# USBtoTTL.net
KiCad netlist of a schematic drawn in Altium Designer
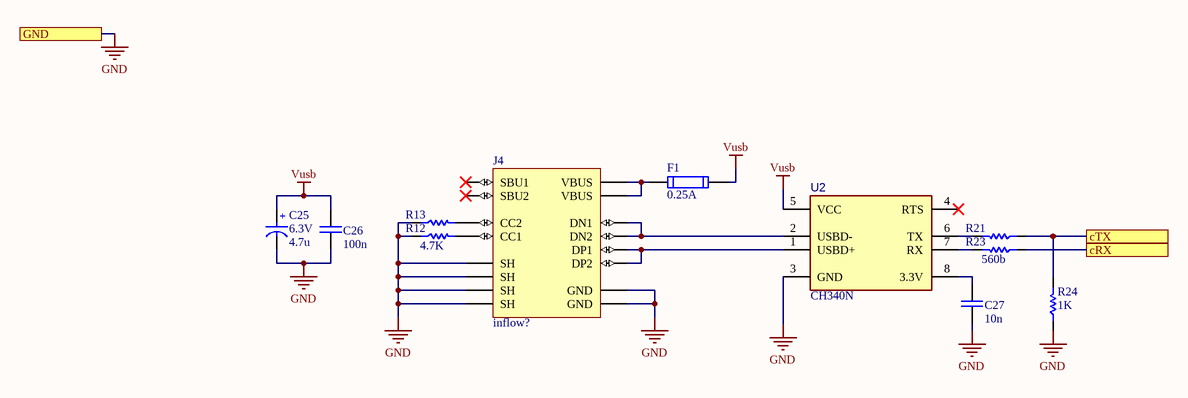
[diagram p0: USBtoTTL.SchDoc]

(export (version "E")
  (design (tool "Eeschema 10.0.6"))
  (components
    (comp (ref "C25")
      (value "4.7u")
      (footprint "SMT_C_Tantalum_A")
      (description "Tantalum Capacitor,TAJ Series-SMD")
      (fields (field (name "RATING") "6.3V") (field (name "Comment") "DS1307"))
      (libsource (lib "aKaReZa") (part "Cap_Tantalum"))
    )
    (comp (ref "C26")
      (value "100n")
      (footprint "CAP 0805/2012")
      (description "Bipolar ceramic capacitor SMD")
      (fields (field (name "Comment") "DS1307"))
      (libsource (lib "aKaReZa") (part "Cap_Multi_SMD_100nF_0805"))
    )
    (comp (ref "C27")
      (value "10n")
      (footprint "CAP 0805/2012")
      (description "Bipolar ceramic capacitor SMD")
      (libsource (lib "aKaReZa") (part "Cap_Multi_SMD_100nF_0805"))
    )
    (comp (ref "F1")
      (value "0.25A")
      (footprint "1206_F")
      (description "Short circiut  protection")
      (libsource (lib "aKaReZa") (part "Other_Elec_Fuse_SMD"))
    )
    (comp (ref "J4")
      (value "16b")
      (footprint "USBC_SMD_16_USB4110 - Extended")
      (description "USB C Female Connector")
      (fields (field (name "INFLOW") "inflow?") (field (name "VALIDATION") "NT"))
      (libsource (lib "aKaReZa") (part "Con_USB_C_16P"))
    )
    (comp (ref "R12")
      (value "4.7K")
      (footprint "RES 0805 (2012X06L)")
      (description "Resistor")
      (libsource (lib "aKaReZa") (part "Res_SMD_0805"))
    )
    (comp (ref "R13")
      (value "4.7K")
      (footprint "RES 0805 (2012X06L)")
      (description "Resistor")
      (libsource (lib "aKaReZa") (part "Res_SMD_0805"))
    )
    (comp (ref "R21")
      (value "560b")
      (footprint "RES 0805 (2012X06L)")
      (description "Resistor")
      (libsource (lib "aKaReZa") (part "Res_SMD_0805"))
    )
    (comp (ref "R23")
      (value "560b")
      (footprint "RES 0805 (2012X06L)")
      (description "Resistor")
      (libsource (lib "aKaReZa") (part "Res_SMD_0805"))
    )
    (comp (ref "R24")
      (value "1K")
      (footprint "RES 0805 (2012X06L)")
      (description "Resistor")
      (libsource (lib "aKaReZa") (part "Res_SMD_0805"))
    )
    (comp (ref "U2")
      (value "CH340N")
      (footprint "SO8_narrow_m")
      (description "TTL To USB Chip")
      (libsource (lib "aKaReZa") (part "IC_Converter_CH340N"))
    )
  )
  (nets
    (net (code "1") (name "/cRX") (class "Default")
      (node (ref "R23") (pin "1") (pinfunction "1_1") (pintype "passive"))
    )
    (net (code "2") (name "/cTX") (class "Default")
      (node (ref "R21") (pin "1") (pinfunction "1_1") (pintype "passive"))
      (node (ref "R24") (pin "2") (pinfunction "2_2") (pintype "passive"))
    )
    (net (code "3") (name "GND") (class "Default")
      (node (ref "C25") (pin "2") (pinfunction "-_2") (pintype "passive"))
      (node (ref "C26") (pin "2") (pinfunction "2_2") (pintype "passive"))
      (node (ref "C27") (pin "2") (pinfunction "2_2") (pintype "passive"))
      (node (ref "J4") (pin "A1B12") (pinfunction "GND_A1B12") (pintype "power_in"))
      (node (ref "J4") (pin "B1A12") (pinfunction "GND_B1A12") (pintype "power_in"))
      (node (ref "J4") (pin "S1") (pinfunction "SH_S1") (pintype "power_in"))
      (node (ref "J4") (pin "S2") (pinfunction "SH_S2") (pintype "power_in"))
      (node (ref "J4") (pin "S3") (pinfunction "SH_S3") (pintype "power_in"))
      (node (ref "J4") (pin "S4") (pinfunction "SH_S4") (pintype "power_in"))
      (node (ref "R12") (pin "1") (pinfunction "1_1") (pintype "passive"))
      (node (ref "R13") (pin "1") (pinfunction "1_1") (pintype "passive"))
      (node (ref "R24") (pin "1") (pinfunction "1_1") (pintype "passive"))
      (node (ref "U2") (pin "3") (pinfunction "GND_3") (pintype "passive"))
    )
    (net (code "4") (name "Net-(F1-Pad1)") (class "Default")
      (node (ref "F1") (pin "1") (pinfunction "1_1") (pintype "passive"))
      (node (ref "J4") (pin "A4B9") (pinfunction "VBUS_A4B9") (pintype "power_in"))
      (node (ref "J4") (pin "B4A9") (pinfunction "VBUS_B4A9") (pintype "power_in"))
    )
    (net (code "5") (name "Net-(J4-CC1)") (class "Default")
      (node (ref "J4") (pin "A5") (pinfunction "CC1_A5") (pintype "bidirectional"))
      (node (ref "R12") (pin "2") (pinfunction "2_2") (pintype "passive"))
    )
    (net (code "6") (name "Net-(J4-CC2)") (class "Default")
      (node (ref "J4") (pin "B5") (pinfunction "CC2_B5") (pintype "bidirectional"))
      (node (ref "R13") (pin "2") (pinfunction "2_2") (pintype "passive"))
    )
    (net (code "7") (name "Net-(J4-DN1)") (class "Default")
      (node (ref "J4") (pin "A7") (pinfunction "DN1_A7") (pintype "bidirectional"))
      (node (ref "J4") (pin "B7") (pinfunction "DN2_B7") (pintype "bidirectional"))
      (node (ref "U2") (pin "2") (pinfunction "USBD-_2") (pintype "passive"))
    )
    (net (code "8") (name "Net-(J4-DP1)") (class "Default")
      (node (ref "J4") (pin "A6") (pinfunction "DP1_A6") (pintype "bidirectional"))
      (node (ref "J4") (pin "B6") (pinfunction "DP2_B6") (pintype "bidirectional"))
      (node (ref "U2") (pin "1") (pinfunction "USBD+_1") (pintype "passive"))
    )
    (net (code "9") (name "Net-(U2-3.3V)") (class "Default")
      (node (ref "C27") (pin "1") (pinfunction "1_1") (pintype "passive"))
      (node (ref "U2") (pin "8") (pinfunction "3.3V_8") (pintype "passive"))
    )
    (net (code "10") (name "Net-(U2-RX)") (class "Default")
      (node (ref "R23") (pin "2") (pinfunction "2_2") (pintype "passive"))
      (node (ref "U2") (pin "7") (pinfunction "RX_7") (pintype "passive"))
    )
    (net (code "11") (name "Net-(U2-TX)") (class "Default")
      (node (ref "R21") (pin "2") (pinfunction "2_2") (pintype "passive"))
      (node (ref "U2") (pin "6") (pinfunction "TX_6") (pintype "passive"))
    )
    (net (code "12") (name "Vusb") (class "Default")
      (node (ref "C25") (pin "1") (pinfunction "+_1") (pintype "passive"))
      (node (ref "C26") (pin "1") (pinfunction "1_1") (pintype "passive"))
      (node (ref "F1") (pin "2") (pinfunction "2_2") (pintype "passive"))
      (node (ref "U2") (pin "5") (pinfunction "VCC_5") (pintype "passive"))
    )
    (net (code "13") (name "unconnected-(J4-SBU1-PadA8)") (class "Default")
      (node (ref "J4") (pin "A8") (pinfunction "SBU1_A8") (pintype "bidirectional+no_connect"))
    )
    (net (code "14") (name "unconnected-(J4-SBU2-PadB8)") (class "Default")
      (node (ref "J4") (pin "B8") (pinfunction "SBU2_B8") (pintype "bidirectional+no_connect"))
    )
    (net (code "15") (name "unconnected-(U2-RTS-Pad4)") (class "Default")
      (node (ref "U2") (pin "4") (pinfunction "RTS_4") (pintype "passive+no_connect"))
    )
  )
)
